# DAC_TEST.net
KiCad netlist of a schematic drawn in Altium Designer
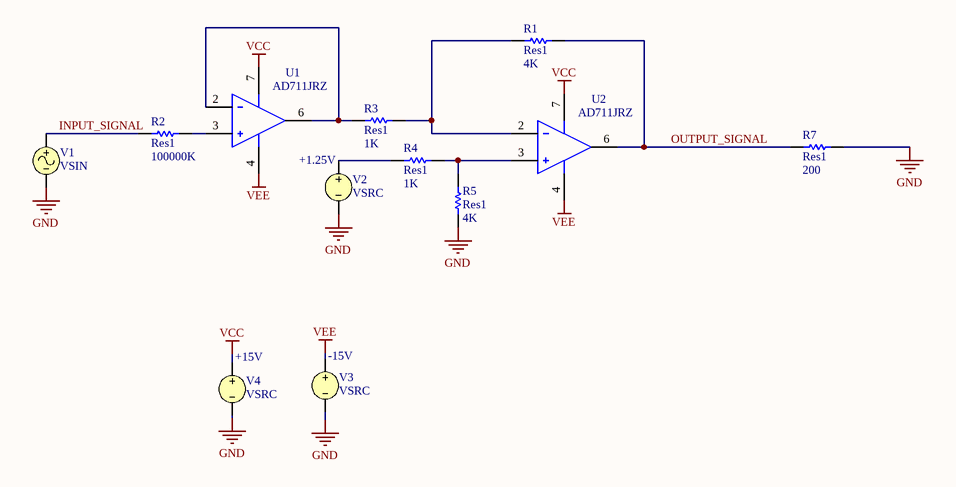
[diagram p0: DAC_TEST.SchDoc]

(export (version "E")
  (design (tool "Eeschema 10.0.6"))
  (components
    (comp (ref "R1")
      (value "Res1")
      (footprint "AXIAL-0.3")
      (description "Resistor")
      (fields (field (name "ALTIUM_VALUE") "4K") (field (name "PUBLISHER") "Altium Limited"))
      (libsource (lib "Miscellaneous Devices") (part "Res1"))
    )
    (comp (ref "R2")
      (value "Res1")
      (footprint "AXIAL-0.3")
      (description "Resistor")
      (fields (field (name "ALTIUM_VALUE") "100000K") (field (name "PUBLISHER") "Altium Limited"))
      (libsource (lib "Miscellaneous Devices") (part "Res1"))
    )
    (comp (ref "R3")
      (value "Res1")
      (footprint "AXIAL-0.3")
      (description "Resistor")
      (fields (field (name "ALTIUM_VALUE") "1K") (field (name "PUBLISHER") "Altium Limited"))
      (libsource (lib "Miscellaneous Devices") (part "Res1"))
    )
    (comp (ref "R4")
      (value "Res1")
      (footprint "AXIAL-0.3")
      (description "Resistor")
      (fields (field (name "ALTIUM_VALUE") "1K") (field (name "PUBLISHER") "Altium Limited"))
      (libsource (lib "Miscellaneous Devices") (part "Res1"))
    )
    (comp (ref "R5")
      (value "Res1")
      (footprint "AXIAL-0.3")
      (description "Resistor")
      (fields (field (name "ALTIUM_VALUE") "4K") (field (name "PUBLISHER") "Altium Limited"))
      (libsource (lib "Miscellaneous Devices") (part "Res1"))
    )
    (comp (ref "R7")
      (value "Res1")
      (footprint "AXIAL-0.3")
      (description "Resistor")
      (fields (field (name "ALTIUM_VALUE") "200") (field (name "PUBLISHER") "Altium Limited"))
      (libsource (lib "Miscellaneous Devices") (part "Res1"))
    )
    (comp (ref "U1")
      (value "AD711JRZ")
      (description "Operational Amplifier")
      (libsource (lib "CAP_TEST") (part "AD711JRZ"))
    )
    (comp (ref "U2")
      (value "AD711JRZ")
      (description "Operational Amplifier")
      (libsource (lib "CAP_TEST") (part "AD711JRZ"))
    )
    (comp (ref "V1")
      (value "VSIN")
      (description "Sinusoidal Voltage Source")
      (fields (field (name "PUBLISHER") "Altium Limited"))
      (libsource (lib "Simulation Sources") (part "VSIN"))
    )
    (comp (ref "V2")
      (value "VSRC")
      (description "Voltage Source")
      (fields (field (name "ALTIUM_VALUE") "+1.25V") (field (name "PUBLISHER") "Altium Limited"))
      (libsource (lib "Simulation Sources") (part "VSRC"))
    )
    (comp (ref "V3")
      (value "VSRC")
      (description "Voltage Source")
      (fields (field (name "ALTIUM_VALUE") "-15V") (field (name "PUBLISHER") "Altium Limited"))
      (libsource (lib "Simulation Sources") (part "VSRC"))
    )
    (comp (ref "V4")
      (value "VSRC")
      (description "Voltage Source")
      (fields (field (name "ALTIUM_VALUE") "+15V") (field (name "PUBLISHER") "Altium Limited"))
      (libsource (lib "Simulation Sources") (part "VSRC"))
    )
  )
  (nets
    (net (code "1") (name "/INPUT_SIGNAL") (class "Default")
      (node (ref "R2") (pin "1") (pinfunction "1_1") (pintype "passive"))
      (node (ref "V1") (pin "1") (pinfunction "1_1") (pintype "passive"))
    )
    (net (code "2") (name "/OUTPUT_SIGNAL") (class "Default")
      (node (ref "R1") (pin "2") (pinfunction "2_2") (pintype "passive"))
      (node (ref "R7") (pin "1") (pinfunction "1_1") (pintype "passive"))
      (node (ref "U2") (pin "6") (pinfunction "OUT_6") (pintype "passive"))
    )
    (net (code "3") (name "GND") (class "Default")
      (node (ref "R5") (pin "1") (pinfunction "1_1") (pintype "passive"))
      (node (ref "R7") (pin "2") (pinfunction "2_2") (pintype "passive"))
      (node (ref "V1") (pin "2") (pinfunction "2_2") (pintype "passive"))
      (node (ref "V2") (pin "2") (pinfunction "2_2") (pintype "passive"))
      (node (ref "V3") (pin "2") (pinfunction "2_2") (pintype "passive"))
      (node (ref "V4") (pin "2") (pinfunction "2_2") (pintype "passive"))
    )
    (net (code "4") (name "Net-(R4-Pad1)") (class "Default")
      (node (ref "R4") (pin "1") (pinfunction "1_1") (pintype "passive"))
      (node (ref "V2") (pin "1") (pinfunction "1_1") (pintype "passive"))
    )
    (net (code "5") (name "Net-(U1-INV)") (class "Default")
      (node (ref "R3") (pin "1") (pinfunction "1_1") (pintype "passive"))
      (node (ref "U1") (pin "2") (pinfunction "INV_2") (pintype "passive"))
      (node (ref "U1") (pin "6") (pinfunction "OUT_6") (pintype "passive"))
    )
    (net (code "6") (name "Net-(U1-NONINV)") (class "Default")
      (node (ref "R2") (pin "2") (pinfunction "2_2") (pintype "passive"))
      (node (ref "U1") (pin "3") (pinfunction "NONINV_3") (pintype "passive"))
    )
    (net (code "7") (name "Net-(U2-INV)") (class "Default")
      (node (ref "R1") (pin "1") (pinfunction "1_1") (pintype "passive"))
      (node (ref "R3") (pin "2") (pinfunction "2_2") (pintype "passive"))
      (node (ref "U2") (pin "2") (pinfunction "INV_2") (pintype "passive"))
    )
    (net (code "8") (name "Net-(U2-NONINV)") (class "Default")
      (node (ref "R4") (pin "2") (pinfunction "2_2") (pintype "passive"))
      (node (ref "R5") (pin "2") (pinfunction "2_2") (pintype "passive"))
      (node (ref "U2") (pin "3") (pinfunction "NONINV_3") (pintype "passive"))
    )
    (net (code "9") (name "VCC") (class "Default")
      (node (ref "U1") (pin "7") (pinfunction "VCC_7") (pintype "passive"))
      (node (ref "U2") (pin "7") (pinfunction "VCC_7") (pintype "passive"))
      (node (ref "V4") (pin "1") (pinfunction "1_1") (pintype "passive"))
    )
    (net (code "10") (name "VEE") (class "Default")
      (node (ref "U1") (pin "4") (pinfunction "VEE_4") (pintype "passive"))
      (node (ref "U2") (pin "4") (pinfunction "VEE_4") (pintype "passive"))
      (node (ref "V3") (pin "1") (pinfunction "1_1") (pintype "passive"))
    )
  )
)
